# PopAudio.net
KiCad netlist of a schematic drawn in Altium Designer
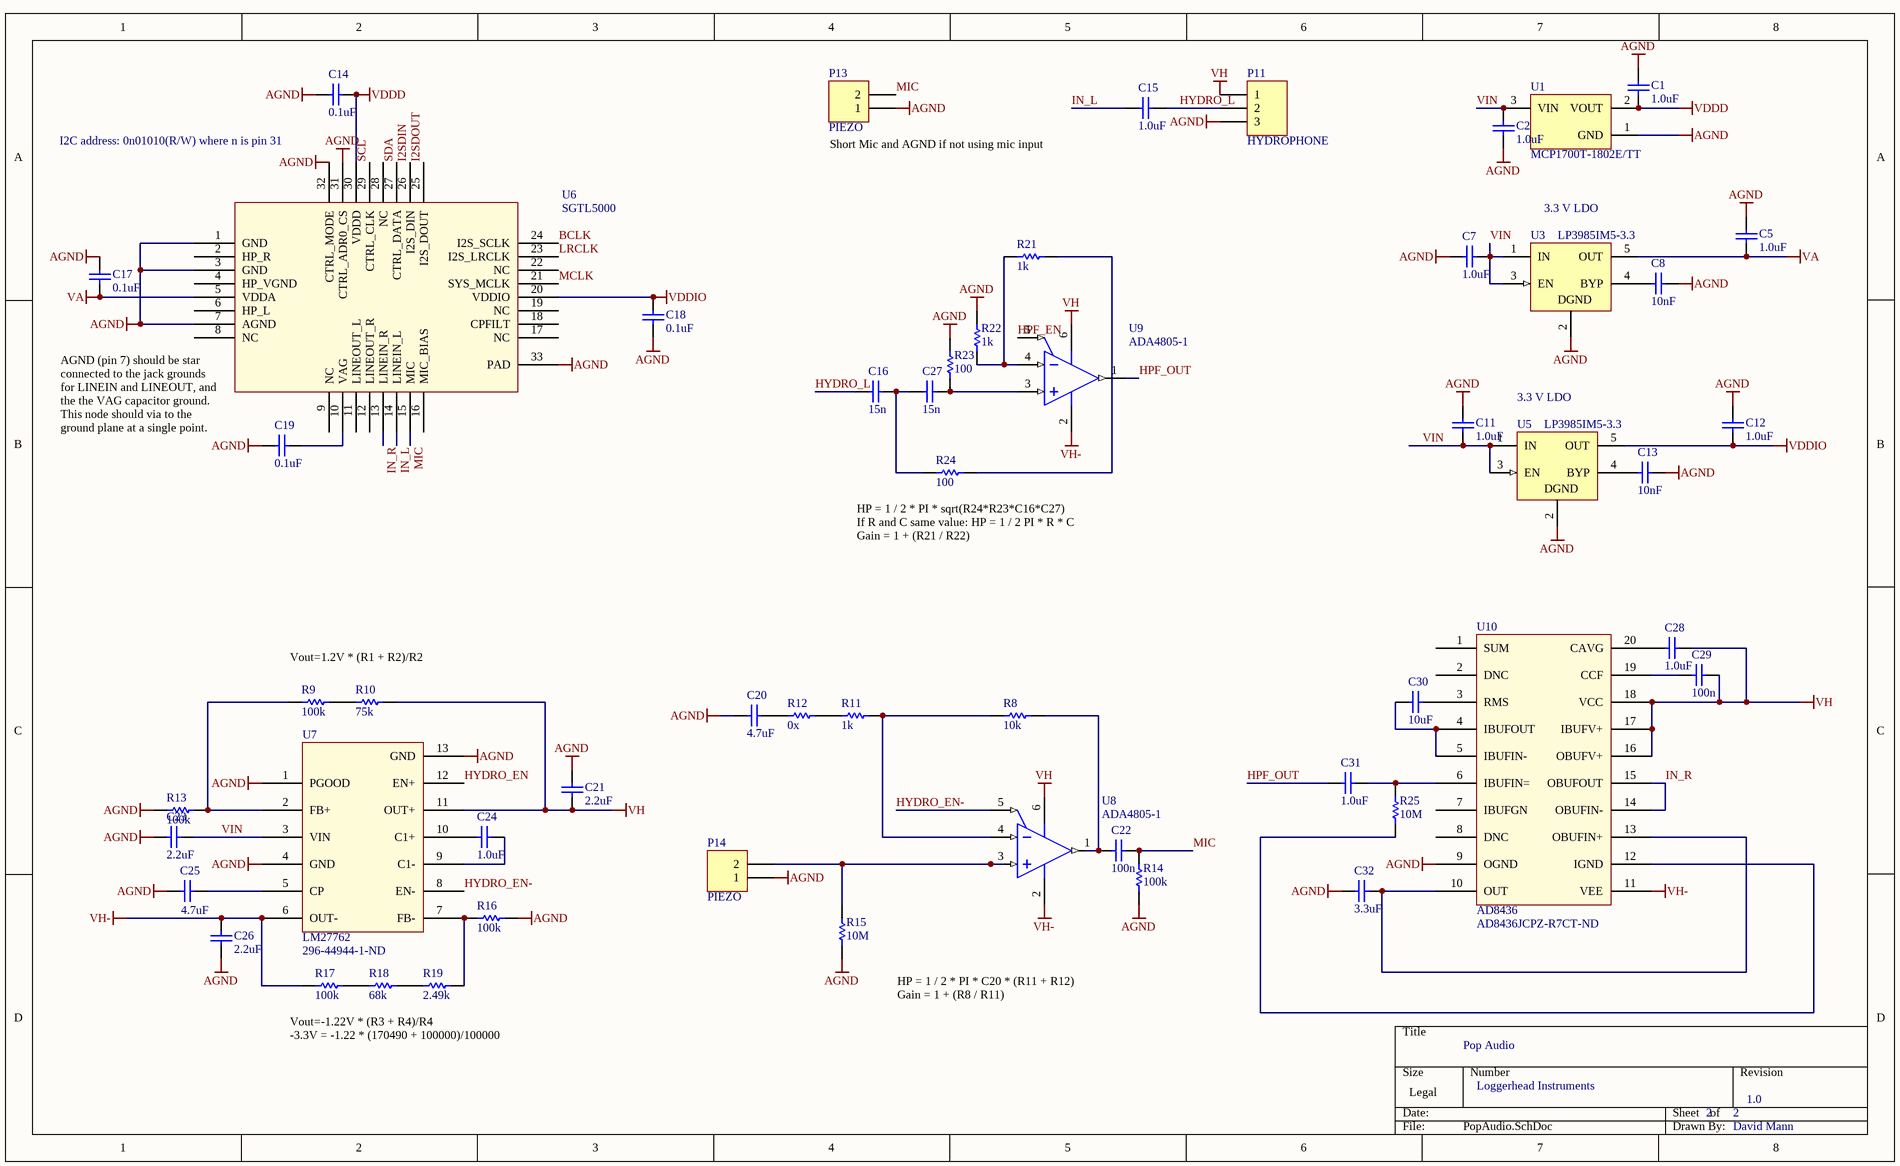
[diagram p0: PopAudio.SchDoc]

(export (version "E")
  (design (tool "Eeschema 10.0.6"))
  (components
    (comp (ref "C1")
      (value "1.0uF")
      (footprint "0402")
      (description "Ceramic Chip Capacitor - Standard")
      (fields (field (name "PUBLISHER") "Altium Limited"))
      (libsource (lib "KEMET Chip Capacitor") (part "C0402"))
    )
    (comp (ref "C2")
      (value "1.0uF")
      (footprint "0402")
      (description "Ceramic Chip Capacitor - Standard")
      (fields (field (name "PUBLISHER") "Altium Limited"))
      (libsource (lib "KEMET Chip Capacitor") (part "C0402"))
    )
    (comp (ref "C5")
      (value "1.0uF")
      (footprint "0402")
      (description "Ceramic Chip Capacitor - Standard")
      (fields (field (name "PUBLISHER") "Altium Limited"))
      (libsource (lib "KEMET Chip Capacitor") (part "C0402"))
    )
    (comp (ref "C7")
      (value "1.0uF")
      (footprint "0402")
      (description "Ceramic Chip Capacitor - Standard")
      (fields (field (name "PUBLISHER") "Altium Limited"))
      (libsource (lib "KEMET Chip Capacitor") (part "C0402"))
    )
    (comp (ref "C8")
      (value "10nF")
      (footprint "0402")
      (description "Ceramic Chip Capacitor - Standard")
      (fields (field (name "PUBLISHER") "Altium Limited"))
      (libsource (lib "KEMET Chip Capacitor") (part "C0402"))
    )
    (comp (ref "C11")
      (value "1.0uF")
      (footprint "0402")
      (description "Ceramic Chip Capacitor - Standard")
      (fields (field (name "PUBLISHER") "Altium Limited"))
      (libsource (lib "KEMET Chip Capacitor") (part "C0402"))
    )
    (comp (ref "C12")
      (value "1.0uF")
      (footprint "0402")
      (description "Ceramic Chip Capacitor - Standard")
      (fields (field (name "PUBLISHER") "Altium Limited"))
      (libsource (lib "KEMET Chip Capacitor") (part "C0402"))
    )
    (comp (ref "C13")
      (value "10nF")
      (footprint "0402")
      (description "Ceramic Chip Capacitor - Standard")
      (fields (field (name "PUBLISHER") "Altium Limited"))
      (libsource (lib "KEMET Chip Capacitor") (part "C0402"))
    )
    (comp (ref "C14")
      (value "0.1uF")
      (footprint "0402")
      (description "Ceramic Chip Capacitor - Standard")
      (fields (field (name "PUBLISHER") "Altium Limited"))
      (libsource (lib "KEMET Chip Capacitor") (part "C0402"))
    )
    (comp (ref "C15")
      (value "1.0uF")
      (footprint "0402")
      (description "Ceramic Chip Capacitor - Standard")
      (fields (field (name "PUBLISHER") "Altium Limited"))
      (libsource (lib "KEMET Chip Capacitor") (part "C0402"))
    )
    (comp (ref "C16")
      (value "15n")
      (footprint "0402")
      (description "Ceramic Chip Capacitor - Standard")
      (fields (field (name "PUBLISHER") "Altium Limited"))
      (libsource (lib "KEMET Chip Capacitor") (part "C0402"))
    )
    (comp (ref "C17")
      (value "0.1uF")
      (footprint "0402")
      (description "Ceramic Chip Capacitor - Standard")
      (fields (field (name "PUBLISHER") "Altium Limited"))
      (libsource (lib "KEMET Chip Capacitor") (part "C0402"))
    )
    (comp (ref "C18")
      (value "0.1uF")
      (footprint "0402")
      (description "Ceramic Chip Capacitor - Standard")
      (fields (field (name "PUBLISHER") "Altium Limited"))
      (libsource (lib "KEMET Chip Capacitor") (part "C0402"))
    )
    (comp (ref "C19")
      (value "0.1uF")
      (footprint "0402")
      (description "Ceramic Chip Capacitor - Standard")
      (fields (field (name "PUBLISHER") "Altium Limited"))
      (libsource (lib "KEMET Chip Capacitor") (part "C0402"))
    )
    (comp (ref "C20")
      (value "4.7uF")
      (footprint "0603")
      (description "Ceramic Chip Capacitor - Standard")
      (fields (field (name "PUBLISHER") "Altium Limited"))
      (libsource (lib "KEMET Chip Capacitor") (part "C0603"))
    )
    (comp (ref "C21")
      (value "2.2uF")
      (footprint "0402")
      (description "Ceramic Chip Capacitor - Standard")
      (fields (field (name "PUBLISHER") "Altium Limited"))
      (libsource (lib "KEMET Chip Capacitor") (part "C0402"))
    )
    (comp (ref "C22")
      (value "100n")
      (footprint "0402")
      (description "Ceramic Chip Capacitor - Standard")
      (fields (field (name "PUBLISHER") "Altium Limited"))
      (libsource (lib "KEMET Chip Capacitor") (part "C0402"))
    )
    (comp (ref "C23")
      (value "2.2uF")
      (footprint "0402")
      (description "Ceramic Chip Capacitor - Standard")
      (fields (field (name "PUBLISHER") "Altium Limited"))
      (libsource (lib "KEMET Chip Capacitor") (part "C0402"))
    )
    (comp (ref "C24")
      (value "1.0uF")
      (footprint "0402")
      (description "Ceramic Chip Capacitor - Standard")
      (fields (field (name "PUBLISHER") "Altium Limited"))
      (libsource (lib "KEMET Chip Capacitor") (part "C0402"))
    )
    (comp (ref "C25")
      (value "4.7uF")
      (footprint "0603")
      (description "Ceramic Chip Capacitor - Standard")
      (fields (field (name "PUBLISHER") "Altium Limited"))
      (libsource (lib "KEMET Chip Capacitor") (part "C0603"))
    )
    (comp (ref "C26")
      (value "2.2uF")
      (footprint "0402")
      (description "Ceramic Chip Capacitor - Standard")
      (fields (field (name "PUBLISHER") "Altium Limited"))
      (libsource (lib "KEMET Chip Capacitor") (part "C0402"))
    )
    (comp (ref "C27")
      (value "15n")
      (footprint "0402")
      (description "Ceramic Chip Capacitor - Standard")
      (fields (field (name "PUBLISHER") "Altium Limited"))
      (libsource (lib "KEMET Chip Capacitor") (part "C0402"))
    )
    (comp (ref "C28")
      (value "1.0uF")
      (footprint "0402")
      (description "Ceramic Chip Capacitor - Standard")
      (fields (field (name "PUBLISHER") "Altium Limited"))
      (libsource (lib "KEMET Chip Capacitor") (part "C0402"))
    )
    (comp (ref "C29")
      (value "100n")
      (footprint "0402")
      (description "Ceramic Chip Capacitor - Standard")
      (fields (field (name "PUBLISHER") "Altium Limited"))
      (libsource (lib "KEMET Chip Capacitor") (part "C0402"))
    )
    (comp (ref "C30")
      (value "10uF")
      (footprint "0402")
      (description "Ceramic Chip Capacitor - Standard")
      (fields (field (name "PUBLISHER") "Altium Limited"))
      (libsource (lib "KEMET Chip Capacitor") (part "C0402"))
    )
    (comp (ref "C31")
      (value "1.0uF")
      (footprint "0402")
      (description "Ceramic Chip Capacitor - Standard")
      (fields (field (name "PUBLISHER") "Altium Limited"))
      (libsource (lib "KEMET Chip Capacitor") (part "C0402"))
    )
    (comp (ref "C32")
      (value "3.3uF")
      (footprint "0402")
      (description "Ceramic Chip Capacitor - Standard")
      (fields (field (name "PUBLISHER") "Altium Limited"))
      (libsource (lib "KEMET Chip Capacitor") (part "C0402"))
    )
    (comp (ref "P11")
      (value "HYDROPHONE")
      (footprint "HDR1X3")
      (description "Header, 3-Pin")
      (fields (field (name "PUBLISHER") "Altium Limited"))
      (libsource (lib "Miscellaneous Connectors") (part "Header 3"))
    )
    (comp (ref "P13")
      (value "PIEZO")
      (footprint "HDR1X2")
      (description "Header, 2-Pin")
      (fields (field (name "PUBLISHER") "Altium Limited"))
      (libsource (lib "Miscellaneous Connectors") (part "Header 2"))
    )
    (comp (ref "P14")
      (value "PIEZO")
      (footprint "HDR1X2")
      (description "Header, 2-Pin")
      (fields (field (name "PUBLISHER") "Altium Limited"))
      (libsource (lib "Miscellaneous Connectors") (part "Header 2"))
    )
    (comp (ref "R8")
      (value "10k")
      (footprint "3-0603")
      (fields (field (name "PUBLISHER") "Altium Limited"))
      (libsource (lib "Panasonic Resistor") (part "ERJ3RK"))
    )
    (comp (ref "R9")
      (value "100k")
      (footprint "3-0603")
      (fields (field (name "PUBLISHER") "Altium Limited"))
      (libsource (lib "Panasonic Resistor") (part "ERJ3RK"))
    )
    (comp (ref "R10")
      (value "75k")
      (footprint "3-0603")
      (fields (field (name "PUBLISHER") "Altium Limited"))
      (libsource (lib "Panasonic Resistor") (part "ERJ3RK"))
    )
    (comp (ref "R11")
      (value "1k")
      (footprint "3-0603")
      (fields (field (name "PUBLISHER") "Altium Limited"))
      (libsource (lib "Panasonic Resistor") (part "ERJ3RK"))
    )
    (comp (ref "R12")
      (value "0x")
      (footprint "3-0603")
      (fields (field (name "PUBLISHER") "Altium Limited"))
      (libsource (lib "Panasonic Resistor") (part "ERJ3RK"))
    )
    (comp (ref "R13")
      (value "100k")
      (footprint "3-0603")
      (fields (field (name "PUBLISHER") "Altium Limited"))
      (libsource (lib "Panasonic Resistor") (part "ERJ3RK"))
    )
    (comp (ref "R14")
      (value "100k")
      (footprint "3-0603")
      (fields (field (name "PUBLISHER") "Altium Limited"))
      (libsource (lib "Panasonic Resistor") (part "ERJ3RK"))
    )
    (comp (ref "R15")
      (value "10M")
      (footprint "3-0603")
      (fields (field (name "PUBLISHER") "Altium Limited"))
      (libsource (lib "Panasonic Resistor") (part "ERJ3RK"))
    )
    (comp (ref "R16")
      (value "100k")
      (footprint "3-0603")
      (fields (field (name "PUBLISHER") "Altium Limited"))
      (libsource (lib "Panasonic Resistor") (part "ERJ3RK"))
    )
    (comp (ref "R17")
      (value "100k")
      (footprint "3-0603")
      (fields (field (name "PUBLISHER") "Altium Limited"))
      (libsource (lib "Panasonic Resistor") (part "ERJ3RK"))
    )
    (comp (ref "R18")
      (value "68k")
      (footprint "3-0603")
      (fields (field (name "PUBLISHER") "Altium Limited"))
      (libsource (lib "Panasonic Resistor") (part "ERJ3RK"))
    )
    (comp (ref "R19")
      (value "2.49k")
      (footprint "3-0603")
      (fields (field (name "PUBLISHER") "Altium Limited"))
      (libsource (lib "Panasonic Resistor") (part "ERJ3RK"))
    )
    (comp (ref "R21")
      (value "1k")
      (footprint "3-0603")
      (fields (field (name "PUBLISHER") "Altium Limited"))
      (libsource (lib "Panasonic Resistor") (part "ERJ3RK"))
    )
    (comp (ref "R22")
      (value "1k")
      (footprint "3-0603")
      (fields (field (name "PUBLISHER") "Altium Limited"))
      (libsource (lib "Panasonic Resistor") (part "ERJ3RK"))
    )
    (comp (ref "R23")
      (value "100")
      (footprint "3-0603")
      (fields (field (name "PUBLISHER") "Altium Limited"))
      (libsource (lib "Panasonic Resistor") (part "ERJ3RK"))
    )
    (comp (ref "R24")
      (value "100")
      (footprint "3-0603")
      (fields (field (name "PUBLISHER") "Altium Limited"))
      (libsource (lib "Panasonic Resistor") (part "ERJ3RK"))
    )
    (comp (ref "R25")
      (value "10M")
      (footprint "3-0603")
      (fields (field (name "PUBLISHER") "Altium Limited"))
      (libsource (lib "Panasonic Resistor") (part "ERJ3RK"))
    )
    (comp (ref "U1")
      (value "MCP1700T-1802E/TT")
      (footprint "SOT-23-TT3_N")
      (description "Low Quiescent Current LDO, 3-Pin SOT-23, Extended Temperature, Tape and Reel")
      (fields (field (name "MANUFACTURER") "Microchip"))
      (libsource (lib "Microchip Power Management Line Regulator") (part "MCP1700T-1802E/TT"))
    )
    (comp (ref "U3")
      (value "LP3985IM5-3.3")
      (footprint "MF05A_N")
      (description "Micropower, 150mA Low-Noise Ultra Low-Dropout CMOS Voltage Regulator")
      (fields
        (field (name "MANUFACTURER") "National Semiconductor")
        (field (name "DIGIKEYPARTNUMBER") "LP3985IM5-3.3CT-ND")
        (field (name "PUBLISHER") "Altium Limited")
      )
      (libsource (lib "NSC LDO") (part "LP3985IM5-3.3"))
    )
    (comp (ref "U5")
      (value "LP3985IM5-3.3")
      (footprint "MF05A_N")
      (description "Micropower, 150mA Low-Noise Ultra Low-Dropout CMOS Voltage Regulator")
      (fields
        (field (name "MANUFACTURER") "National Semiconductor")
        (field (name "DIGIKEYPARTNUMBER") "LP3985IM5-3.3CT-ND")
        (field (name "PUBLISHER") "Altium Limited")
      )
      (libsource (lib "NSC LDO") (part "LP3985IM5-3.3"))
    )
    (comp (ref "U6") (value "SGTL5000") (footprint "QFN32") (libsource (lib "Loggerhead") (part "SGTL5000")))
    (comp (ref "U7")
      (value "LM27762")
      (footprint "SOP12")
      (description "Pos and Neg Output Charge pump plus LDO")
      (fields (field (name "SUPPLIER PART NUMBER 1") "296-44944-1-ND"))
      (libsource (lib "Loggerhead") (part "LM27762"))
    )
    (comp (ref "U8")
      (value "ADA4805-1")
      (footprint "ADI-RJ-6_N")
      (fields
        (field (name "GENERIC PART NUMBER") "ADA4841-1")
        (field (name "MANUFACTURER") "Analog Devices")
        (field (name "PARTNUMBER") "ADA4841-1YRJZ-RL")
      )
      (libsource (lib "Analog Devices Operational Amplifiers") (part "ADA4841-1YRJZ-RL"))
    )
    (comp (ref "U9")
      (value "ADA4805-1")
      (footprint "ADI-RJ-6_N")
      (fields
        (field (name "GENERIC PART NUMBER") "ADA4841-1")
        (field (name "MANUFACTURER") "Analog Devices")
        (field (name "PARTNUMBER") "ADA4841-1YRJZ-RL")
      )
      (libsource (lib "Analog Devices Operational Amplifiers") (part "ADA4841-1YRJZ-RL"))
    )
    (comp (ref "U10")
      (value "AD8436")
      (footprint "AD8436")
      (description "RMS to DC")
      (fields (field (name "SUPPLIER PART NUMBER 1") "AD8436JCPZ-R7CT-ND"))
      (libsource (lib "Loggerhead") (part "AD8436"))
    )
  )
  (nets
    (net (code "1") (name "/BCLK") (class "Default")
      (node (ref "U6") (pin "24") (pinfunction "I2S_SCLK_24") (pintype "passive"))
    )
    (net (code "2") (name "/HPF_EN") (class "Default")
      (node (ref "U9") (pin "5") (pinfunction "~{POWER_DOWN}_5") (pintype "input"))
    )
    (net (code "3") (name "/HPF_OUT") (class "Default")
      (node (ref "C31") (pin "2") (pinfunction "2_2") (pintype "passive"))
      (node (ref "U9") (pin "1") (pinfunction "VOUT_1") (pintype "output"))
    )
    (net (code "4") (name "/HYDRO_EN") (class "Default")
      (node (ref "U7") (pin "12") (pinfunction "EN+_12") (pintype "passive"))
    )
    (net (code "5") (name "/HYDRO_EN-") (class "Default")
      (node (ref "U7") (pin "8") (pinfunction "EN-_8") (pintype "passive"))
      (node (ref "U8") (pin "5") (pinfunction "~{POWER_DOWN}_5") (pintype "input"))
    )
    (net (code "6") (name "/HYDRO_L") (class "Default")
      (node (ref "C15") (pin "1") (pinfunction "1_1") (pintype "passive"))
      (node (ref "C16") (pin "1") (pinfunction "1_1") (pintype "passive"))
      (node (ref "P11") (pin "2") (pinfunction "2_2") (pintype "passive"))
    )
    (net (code "7") (name "/I2SDIN") (class "Default")
      (node (ref "U6") (pin "26") (pinfunction "I2S_DIN_26") (pintype "passive"))
    )
    (net (code "8") (name "/I2SDOUT") (class "Default")
      (node (ref "U6") (pin "25") (pinfunction "I2S_DOUT_25") (pintype "passive"))
    )
    (net (code "9") (name "/IN_L") (class "Default")
      (node (ref "C15") (pin "2") (pinfunction "2_2") (pintype "passive"))
      (node (ref "U6") (pin "14") (pinfunction "LINEIN_L_14") (pintype "passive"))
    )
    (net (code "10") (name "/IN_R") (class "Default")
      (node (ref "U10") (pin "14") (pinfunction "OBUFIN-_14") (pintype "passive"))
      (node (ref "U10") (pin "15") (pinfunction "OBUFOUT_15") (pintype "passive"))
      (node (ref "U6") (pin "13") (pinfunction "LINEIN_R_13") (pintype "passive"))
    )
    (net (code "11") (name "/LRCLK") (class "Default")
      (node (ref "U6") (pin "23") (pinfunction "I2S_LRCLK_23") (pintype "passive"))
    )
    (net (code "12") (name "/MCLK") (class "Default")
      (node (ref "U6") (pin "21") (pinfunction "SYS_MCLK_21") (pintype "passive"))
    )
    (net (code "13") (name "/MIC") (class "Default")
      (node (ref "C22") (pin "2") (pinfunction "2_2") (pintype "passive"))
      (node (ref "P13") (pin "2") (pinfunction "2_2") (pintype "passive"))
      (node (ref "R14") (pin "1") (pinfunction "1_1") (pintype "passive"))
      (node (ref "U6") (pin "15") (pinfunction "MIC_15") (pintype "passive"))
    )
    (net (code "14") (name "/SCL") (class "Default")
      (node (ref "U6") (pin "29") (pinfunction "CTRL_CLK_29") (pintype "passive"))
    )
    (net (code "15") (name "/SDA") (class "Default")
      (node (ref "U6") (pin "27") (pinfunction "CTRL_DATA_27") (pintype "passive"))
    )
    (net (code "16") (name "/VIN") (class "Default")
      (node (ref "C11") (pin "1") (pinfunction "1_1") (pintype "passive"))
      (node (ref "C2") (pin "1") (pinfunction "1_1") (pintype "passive"))
      (node (ref "C23") (pin "1") (pinfunction "1_1") (pintype "passive"))
      (node (ref "C7") (pin "1") (pinfunction "1_1") (pintype "passive"))
      (node (ref "U1") (pin "3") (pinfunction "VIN_3") (pintype "power_in"))
      (node (ref "U3") (pin "1") (pinfunction "IN_1") (pintype "power_in"))
      (node (ref "U3") (pin "3") (pinfunction "EN_3") (pintype "input"))
      (node (ref "U5") (pin "1") (pinfunction "IN_1") (pintype "power_in"))
      (node (ref "U5") (pin "3") (pinfunction "EN_3") (pintype "input"))
      (node (ref "U7") (pin "3") (pinfunction "VIN_3") (pintype "passive"))
    )
    (net (code "17") (name "AGND") (class "Default")
      (node (ref "C1") (pin "2") (pinfunction "2_2") (pintype "passive"))
      (node (ref "C11") (pin "2") (pinfunction "2_2") (pintype "passive"))
      (node (ref "C12") (pin "2") (pinfunction "2_2") (pintype "passive"))
      (node (ref "C13") (pin "1") (pinfunction "1_1") (pintype "passive"))
      (node (ref "C14") (pin "2") (pinfunction "2_2") (pintype "passive"))
      (node (ref "C17") (pin "2") (pinfunction "2_2") (pintype "passive"))
      (node (ref "C18") (pin "2") (pinfunction "2_2") (pintype "passive"))
      (node (ref "C19") (pin "2") (pinfunction "2_2") (pintype "passive"))
      (node (ref "C2") (pin "2") (pinfunction "2_2") (pintype "passive"))
      (node (ref "C20") (pin "2") (pinfunction "2_2") (pintype "passive"))
      (node (ref "C21") (pin "2") (pinfunction "2_2") (pintype "passive"))
      (node (ref "C23") (pin "2") (pinfunction "2_2") (pintype "passive"))
      (node (ref "C25") (pin "1") (pinfunction "1_1") (pintype "passive"))
      (node (ref "C26") (pin "2") (pinfunction "2_2") (pintype "passive"))
      (node (ref "C32") (pin "2") (pinfunction "2_2") (pintype "passive"))
      (node (ref "C5") (pin "2") (pinfunction "2_2") (pintype "passive"))
      (node (ref "C7") (pin "2") (pinfunction "2_2") (pintype "passive"))
      (node (ref "C8") (pin "1") (pinfunction "1_1") (pintype "passive"))
      (node (ref "P11") (pin "3") (pinfunction "3_3") (pintype "passive"))
      (node (ref "P13") (pin "1") (pinfunction "1_1") (pintype "passive"))
      (node (ref "P14") (pin "1") (pinfunction "1_1") (pintype "passive"))
      (node (ref "R13") (pin "1") (pinfunction "1_1") (pintype "passive"))
      (node (ref "R14") (pin "2") (pinfunction "2_2") (pintype "passive"))
      (node (ref "R15") (pin "2") (pinfunction "2_2") (pintype "passive"))
      (node (ref "R16") (pin "2") (pinfunction "2_2") (pintype "passive"))
      (node (ref "R22") (pin "2") (pinfunction "2_2") (pintype "passive"))
      (node (ref "R23") (pin "2") (pinfunction "2_2") (pintype "passive"))
      (node (ref "U1") (pin "1") (pinfunction "GND_1") (pintype "power_in"))
      (node (ref "U10") (pin "9") (pinfunction "OGND_9") (pintype "passive"))
      (node (ref "U3") (pin "2") (pinfunction "GND_2") (pintype "power_in"))
      (node (ref "U5") (pin "2") (pinfunction "GND_2") (pintype "power_in"))
      (node (ref "U6") (pin "1") (pinfunction "GND_1") (pintype "passive"))
      (node (ref "U6") (pin "3") (pinfunction "GND_3") (pintype "passive"))
      (node (ref "U6") (pin "31") (pinfunction "CTRL_ADR0_CS_31") (pintype "passive"))
      (node (ref "U6") (pin "32") (pinfunction "CTRL_MODE_32") (pintype "passive"))
      (node (ref "U6") (pin "33") (pinfunction "PAD_33") (pintype "passive"))
      (node (ref "U6") (pin "7") (pinfunction "AGND_7") (pintype "passive"))
      (node (ref "U7") (pin "1") (pinfunction "PGOOD_1") (pintype "passive"))
      (node (ref "U7") (pin "13") (pinfunction "GND_13") (pintype "passive"))
      (node (ref "U7") (pin "4") (pinfunction "GND_4") (pintype "passive"))
    )
    (net (code "18") (name "Net-(C16-Pad2)") (class "Default")
      (node (ref "C16") (pin "2") (pinfunction "2_2") (pintype "passive"))
      (node (ref "C27") (pin "1") (pinfunction "1_1") (pintype "passive"))
      (node (ref "R24") (pin "1") (pinfunction "1_1") (pintype "passive"))
    )
    (net (code "19") (name "Net-(C20-Pad1)") (class "Default")
      (node (ref "C20") (pin "1") (pinfunction "1_1") (pintype "passive"))
      (node (ref "R12") (pin "1") (pinfunction "1_1") (pintype "passive"))
    )
    (net (code "20") (name "Net-(R10-Pad1)") (class "Default")
      (node (ref "R10") (pin "1") (pinfunction "1_1") (pintype "passive"))
      (node (ref "R9") (pin "2") (pinfunction "2_2") (pintype "passive"))
    )
    (net (code "21") (name "Net-(R11-Pad1)") (class "Default")
      (node (ref "R11") (pin "1") (pinfunction "1_1") (pintype "passive"))
      (node (ref "R12") (pin "2") (pinfunction "2_2") (pintype "passive"))
    )
    (net (code "22") (name "Net-(R17-Pad1)") (class "Default")
      (node (ref "R17") (pin "1") (pinfunction "1_1") (pintype "passive"))
      (node (ref "R18") (pin "2") (pinfunction "2_2") (pintype "passive"))
    )
    (net (code "23") (name "Net-(R18-Pad1)") (class "Default")
      (node (ref "R18") (pin "1") (pinfunction "1_1") (pintype "passive"))
      (node (ref "R19") (pin "2") (pinfunction "2_2") (pintype "passive"))
    )
    (net (code "24") (name "Net-(R21-Pad2)") (class "Default")
      (node (ref "R21") (pin "2") (pinfunction "2_2") (pintype "passive"))
      (node (ref "R24") (pin "2") (pinfunction "2_2") (pintype "passive"))
    )
    (net (code "25") (name "Net-(U3-BYP)") (class "Default")
      (node (ref "C8") (pin "2") (pinfunction "2_2") (pintype "passive"))
      (node (ref "U3") (pin "4") (pinfunction "BYP_4") (pintype "passive"))
    )
    (net (code "26") (name "Net-(U5-BYP)") (class "Default")
      (node (ref "C13") (pin "2") (pinfunction "2_2") (pintype "passive"))
      (node (ref "U5") (pin "4") (pinfunction "BYP_4") (pintype "passive"))
    )
    (net (code "27") (name "Net-(U6-VAG)") (class "Default")
      (node (ref "C19") (pin "1") (pinfunction "1_1") (pintype "passive"))
      (node (ref "U6") (pin "10") (pinfunction "VAG_10") (pintype "passive"))
    )
    (net (code "28") (name "Net-(U7-C1+)") (class "Default")
      (node (ref "C24") (pin "2") (pinfunction "2_2") (pintype "passive"))
      (node (ref "U7") (pin "10") (pinfunction "C1+_10") (pintype "passive"))
    )
    (net (code "29") (name "Net-(U7-C1-)") (class "Default")
      (node (ref "C24") (pin "1") (pinfunction "1_1") (pintype "passive"))
      (node (ref "U7") (pin "9") (pinfunction "C1-_9") (pintype "passive"))
    )
    (net (code "30") (name "Net-(U7-CP)") (class "Default")
      (node (ref "C25") (pin "2") (pinfunction "2_2") (pintype "passive"))
      (node (ref "U7") (pin "5") (pinfunction "CP_5") (pintype "passive"))
    )
    (net (code "31") (name "Net-(U7-FB+)") (class "Default")
      (node (ref "R13") (pin "2") (pinfunction "2_2") (pintype "passive"))
      (node (ref "R9") (pin "1") (pinfunction "1_1") (pintype "passive"))
      (node (ref "U7") (pin "2") (pinfunction "FB+_2") (pintype "passive"))
    )
    (net (code "32") (name "Net-(U7-FB-)") (class "Default")
      (node (ref "R16") (pin "1") (pinfunction "1_1") (pintype "passive"))
      (node (ref "R19") (pin "1") (pinfunction "1_1") (pintype "passive"))
      (node (ref "U7") (pin "7") (pinfunction "FB-_7") (pintype "passive"))
    )
    (net (code "33") (name "Net-(U8-+IN)") (class "Default")
      (node (ref "P14") (pin "2") (pinfunction "2_2") (pintype "passive"))
      (node (ref "R15") (pin "1") (pinfunction "1_1") (pintype "passive"))
      (node (ref "U8") (pin "3") (pinfunction "+IN_3") (pintype "input"))
    )
    (net (code "34") (name "Net-(U8--IN)") (class "Default")
      (node (ref "R11") (pin "2") (pinfunction "2_2") (pintype "passive"))
      (node (ref "R8") (pin "1") (pinfunction "1_1") (pintype "passive"))
      (node (ref "U8") (pin "4") (pinfunction "-IN_4") (pintype "input"))
    )
    (net (code "35") (name "Net-(U8-VOUT)") (class "Default")
      (node (ref "C22") (pin "1") (pinfunction "1_1") (pintype "passive"))
      (node (ref "R8") (pin "2") (pinfunction "2_2") (pintype "passive"))
      (node (ref "U8") (pin "1") (pinfunction "VOUT_1") (pintype "output"))
    )
    (net (code "36") (name "Net-(U9-+IN)") (class "Default")
      (node (ref "C27") (pin "2") (pinfunction "2_2") (pintype "passive"))
      (node (ref "R23") (pin "1") (pinfunction "1_1") (pintype "passive"))
      (node (ref "U9") (pin "3") (pinfunction "+IN_3") (pintype "input"))
    )
    (net (code "37") (name "Net-(U9--IN)") (class "Default")
      (node (ref "R21") (pin "1") (pinfunction "1_1") (pintype "passive"))
      (node (ref "R22") (pin "1") (pinfunction "1_1") (pintype "passive"))
      (node (ref "U9") (pin "4") (pinfunction "-IN_4") (pintype "input"))
    )
    (net (code "38") (name "Net-(U10-CAVG)") (class "Default")
      (node (ref "C28") (pin "2") (pinfunction "2_2") (pintype "passive"))
      (node (ref "U10") (pin "20") (pinfunction "CAVG_20") (pintype "passive"))
    )
    (net (code "39") (name "Net-(U10-CCF)") (class "Default")
      (node (ref "C29") (pin "1") (pinfunction "1_1") (pintype "passive"))
      (node (ref "U10") (pin "19") (pinfunction "CCF_19") (pintype "passive"))
    )
    (net (code "40") (name "Net-(U10-IBUFIN-)") (class "Default")
      (node (ref "C30") (pin "2") (pinfunction "2_2") (pintype "passive"))
      (node (ref "U10") (pin "4") (pinfunction "IBUFOUT_4") (pintype "passive"))
      (node (ref "U10") (pin "5") (pinfunction "IBUFIN-_5") (pintype "passive"))
    )
    (net (code "41") (name "Net-(U10-IBUFIN=)") (class "Default")
      (node (ref "C31") (pin "1") (pinfunction "1_1") (pintype "passive"))
      (node (ref "R25") (pin "1") (pinfunction "1_1") (pintype "passive"))
      (node (ref "U10") (pin "6") (pinfunction "IBUFIN=_6") (pintype "passive"))
    )
    (net (code "42") (name "Net-(U10-IGND)") (class "Default")
      (node (ref "R25") (pin "2") (pinfunction "2_2") (pintype "passive"))
      (node (ref "U10") (pin "12") (pinfunction "IGND_12") (pintype "passive"))
    )
    (net (code "43") (name "Net-(U10-OBUFIN+)") (class "Default")
      (node (ref "C32") (pin "1") (pinfunction "1_1") (pintype "passive"))
      (node (ref "U10") (pin "10") (pinfunction "OUT_10") (pintype "passive"))
      (node (ref "U10") (pin "13") (pinfunction "OBUFIN+_13") (pintype "passive"))
    )
    (net (code "44") (name "Net-(U10-RMS)") (class "Default")
      (node (ref "C30") (pin "1") (pinfunction "1_1") (pintype "passive"))
      (node (ref "U10") (pin "3") (pinfunction "RMS_3") (pintype "passive"))
    )
    (net (code "45") (name "VA") (class "Default")
      (node (ref "C17") (pin "1") (pinfunction "1_1") (pintype "passive"))
      (node (ref "C5") (pin "1") (pinfunction "1_1") (pintype "passive"))
      (node (ref "U3") (pin "5") (pinfunction "OUT_5") (pintype "power_in"))
      (node (ref "U6") (pin "5") (pinfunction "VDDA_5") (pintype "passive"))
    )
    (net (code "46") (name "VDDD") (class "Default")
      (node (ref "C1") (pin "1") (pinfunction "1_1") (pintype "passive"))
      (node (ref "C14") (pin "1") (pinfunction "1_1") (pintype "passive"))
      (node (ref "U1") (pin "2") (pinfunction "VOUT_2") (pintype "power_in"))
      (node (ref "U6") (pin "30") (pinfunction "VDDD_30") (pintype "passive"))
    )
    (net (code "47") (name "VDDIO") (class "Default")
      (node (ref "C12") (pin "1") (pinfunction "1_1") (pintype "passive"))
      (node (ref "C18") (pin "1") (pinfunction "1_1") (pintype "passive"))
      (node (ref "U5") (pin "5") (pinfunction "OUT_5") (pintype "power_in"))
      (node (ref "U6") (pin "20") (pinfunction "VDDIO_20") (pintype "passive"))
    )
    (net (code "48") (name "VH") (class "Default")
      (node (ref "C21") (pin "1") (pinfunction "1_1") (pintype "passive"))
      (node (ref "C28") (pin "1") (pinfunction "1_1") (pintype "passive"))
      (node (ref "C29") (pin "2") (pinfunction "2_2") (pintype "passive"))
      (node (ref "P11") (pin "1") (pinfunction "1_1") (pintype "passive"))
      (node (ref "R10") (pin "2") (pinfunction "2_2") (pintype "passive"))
      (node (ref "U10") (pin "16") (pinfunction "OBUFV+_16") (pintype "passive"))
      (node (ref "U10") (pin "17") (pinfunction "IBUFV+_17") (pintype "passive"))
      (node (ref "U10") (pin "18") (pinfunction "VCC_18") (pintype "passive"))
      (node (ref "U7") (pin "11") (pinfunction "OUT+_11") (pintype "passive"))
      (node (ref "U8") (pin "6") (pinfunction "+VS_6") (pintype "power_in"))
      (node (ref "U9") (pin "6") (pinfunction "+VS_6") (pintype "power_in"))
    )
    (net (code "49") (name "VH-") (class "Default")
      (node (ref "C26") (pin "1") (pinfunction "1_1") (pintype "passive"))
      (node (ref "R17") (pin "2") (pinfunction "2_2") (pintype "passive"))
      (node (ref "U10") (pin "11") (pinfunction "VEE_11") (pintype "passive"))
      (node (ref "U7") (pin "6") (pinfunction "OUT-_6") (pintype "passive"))
      (node (ref "U8") (pin "2") (pinfunction "-VS_2") (pintype "power_in"))
      (node (ref "U9") (pin "2") (pinfunction "-VS_2") (pintype "power_in"))
    )
    (net (code "50") (name "unconnected-(U6-CPFILT-Pad18)") (class "Default")
      (node (ref "U6") (pin "18") (pinfunction "CPFILT_18") (pintype "passive"))
    )
    (net (code "51") (name "unconnected-(U6-HP_L-Pad6)") (class "Default")
      (node (ref "U6") (pin "6") (pinfunction "HP_L_6") (pintype "passive"))
    )
    (net (code "52") (name "unconnected-(U6-HP_R-Pad2)") (class "Default")
      (node (ref "U6") (pin "2") (pinfunction "HP_R_2") (pintype "passive"))
    )
    (net (code "53") (name "unconnected-(U6-HP_VGND-Pad4)") (class "Default")
      (node (ref "U6") (pin "4") (pinfunction "HP_VGND_4") (pintype "passive"))
    )
    (net (code "54") (name "unconnected-(U6-LINEOUT_L-Pad11)") (class "Default")
      (node (ref "U6") (pin "11") (pinfunction "LINEOUT_L_11") (pintype "passive"))
    )
    (net (code "55") (name "unconnected-(U6-LINEOUT_R-Pad12)") (class "Default")
      (node (ref "U6") (pin "12") (pinfunction "LINEOUT_R_12") (pintype "passive"))
    )
    (net (code "56") (name "unconnected-(U6-MIC_BIAS-Pad16)") (class "Default")
      (node (ref "U6") (pin "16") (pinfunction "MIC_BIAS_16") (pintype "passive"))
    )
    (net (code "57") (name "unconnected-(U6-NC-Pad8)") (class "Default")
      (node (ref "U6") (pin "8") (pinfunction "NC_8") (pintype "passive"))
    )
    (net (code "58") (name "unconnected-(U6-NC-Pad9)") (class "Default")
      (node (ref "U6") (pin "9") (pinfunction "NC_9") (pintype "passive"))
    )
    (net (code "59") (name "unconnected-(U6-NC-Pad17)") (class "Default")
      (node (ref "U6") (pin "17") (pinfunction "NC_17") (pintype "passive"))
    )
    (net (code "60") (name "unconnected-(U6-NC-Pad19)") (class "Default")
      (node (ref "U6") (pin "19") (pinfunction "NC_19") (pintype "passive"))
    )
    (net (code "61") (name "unconnected-(U6-NC-Pad22)") (class "Default")
      (node (ref "U6") (pin "22") (pinfunction "NC_22") (pintype "passive"))
    )
    (net (code "62") (name "unconnected-(U6-NC-Pad28)") (class "Default")
      (node (ref "U6") (pin "28") (pinfunction "NC_28") (pintype "passive"))
    )
    (net (code "63") (name "unconnected-(U10-DNC-Pad2)") (class "Default")
      (node (ref "U10") (pin "2") (pinfunction "DNC_2") (pintype "passive"))
    )
    (net (code "64") (name "unconnected-(U10-DNC-Pad8)") (class "Default")
      (node (ref "U10") (pin "8") (pinfunction "DNC_8") (pintype "passive"))
    )
    (net (code "65") (name "unconnected-(U10-IBUFGN-Pad7)") (class "Default")
      (node (ref "U10") (pin "7") (pinfunction "IBUFGN_7") (pintype "passive"))
    )
    (net (code "66") (name "unconnected-(U10-SUM-Pad1)") (class "Default")
      (node (ref "U10") (pin "1") (pinfunction "SUM_1") (pintype "passive"))
    )
  )
)
